# core2.net
KiCad netlist of a schematic drawn in EAGLE
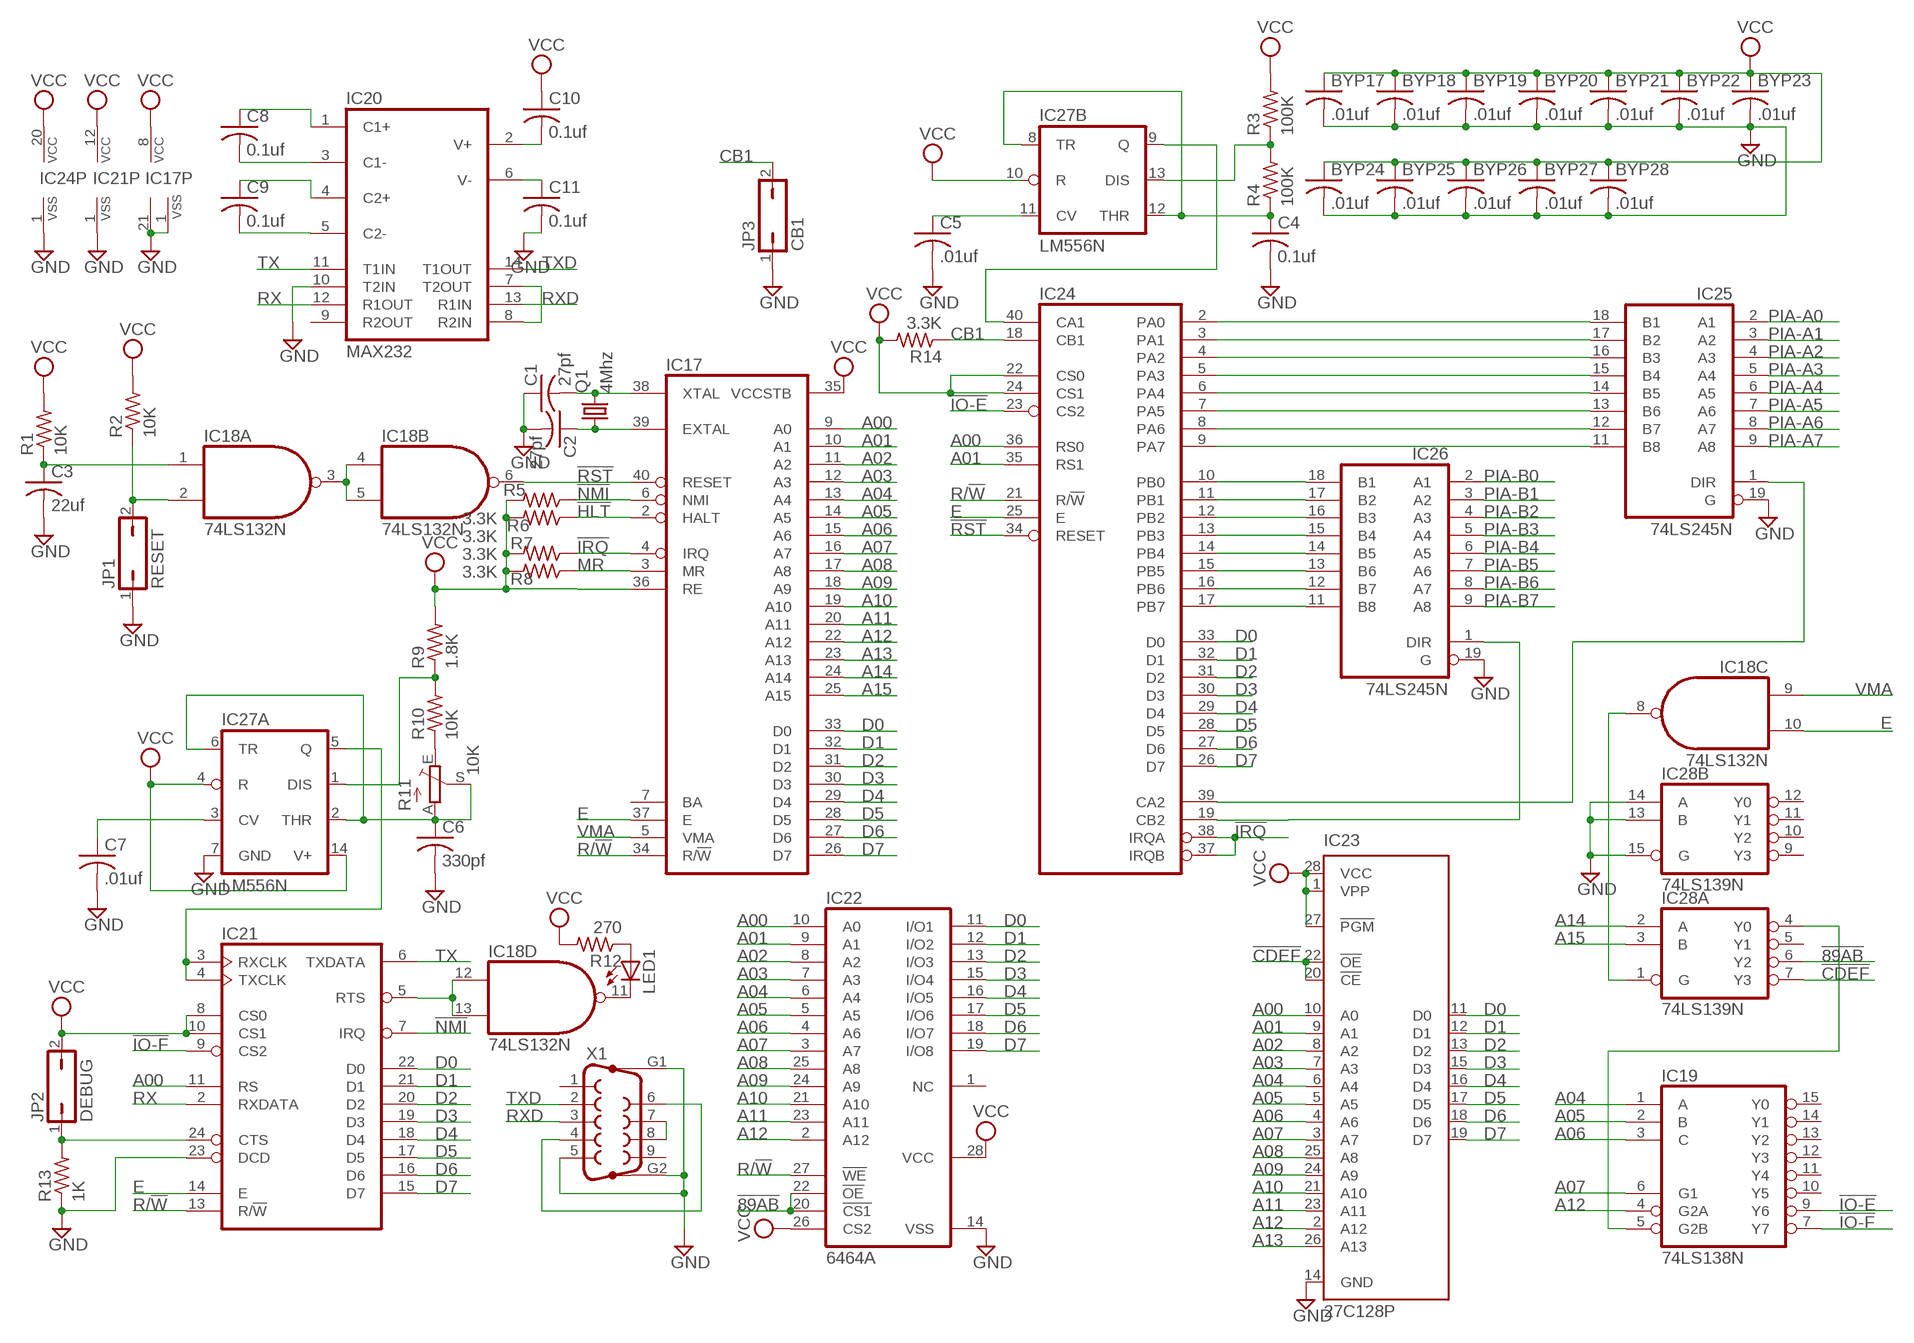
[diagram p0: schematic, sheet 1]
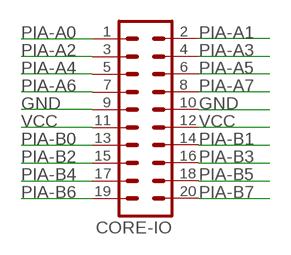
[diagram p1: schematic, sheet 2]

(export (version "E")
  (design (tool "Eeschema 10.0.6"))
  (components
    (comp (ref "CORE-IO")
      (value "MA10-2")
      (footprint "eagle-import:MA10-2")
      (libsource (lib "eagle-import") (part "MA10-2"))
    )
    (comp (ref "BYP17")
      (value ".01uf")
      (footprint "eagle-import:C050-025X075")
      (libsource (lib "eagle-import") (part "C-US050-025X075"))
    )
    (comp (ref "BYP18")
      (value ".01uf")
      (footprint "eagle-import:C050-025X075")
      (libsource (lib "eagle-import") (part "C-US050-025X075"))
    )
    (comp (ref "BYP19")
      (value ".01uf")
      (footprint "eagle-import:C050-025X075")
      (libsource (lib "eagle-import") (part "C-US050-025X075"))
    )
    (comp (ref "BYP20")
      (value ".01uf")
      (footprint "eagle-import:C050-025X075")
      (libsource (lib "eagle-import") (part "C-US050-025X075"))
    )
    (comp (ref "BYP21")
      (value ".01uf")
      (footprint "eagle-import:C050-025X075")
      (libsource (lib "eagle-import") (part "C-US050-025X075"))
    )
    (comp (ref "BYP22")
      (value ".01uf")
      (footprint "eagle-import:C050-025X075")
      (libsource (lib "eagle-import") (part "C-US050-025X075"))
    )
    (comp (ref "BYP23")
      (value ".01uf")
      (footprint "eagle-import:C050-025X075")
      (libsource (lib "eagle-import") (part "C-US050-025X075"))
    )
    (comp (ref "BYP24")
      (value ".01uf")
      (footprint "eagle-import:C050-025X075")
      (libsource (lib "eagle-import") (part "C-US050-025X075"))
    )
    (comp (ref "BYP25")
      (value ".01uf")
      (footprint "eagle-import:C050-025X075")
      (libsource (lib "eagle-import") (part "C-US050-025X075"))
    )
    (comp (ref "BYP26")
      (value ".01uf")
      (footprint "eagle-import:C050-025X075")
      (libsource (lib "eagle-import") (part "C-US050-025X075"))
    )
    (comp (ref "BYP27")
      (value ".01uf")
      (footprint "eagle-import:C050-025X075")
      (libsource (lib "eagle-import") (part "C-US050-025X075"))
    )
    (comp (ref "BYP28")
      (value ".01uf")
      (footprint "eagle-import:C050-025X075")
      (libsource (lib "eagle-import") (part "C-US050-025X075"))
    )
    (comp (ref "C1")
      (value "27pf")
      (footprint "eagle-import:C050-025X075")
      (libsource (lib "eagle-import") (part "C-US050-025X075"))
    )
    (comp (ref "C2")
      (value "27pf")
      (footprint "eagle-import:C050-025X075")
      (libsource (lib "eagle-import") (part "C-US050-025X075"))
    )
    (comp (ref "C3")
      (value "22uf")
      (footprint "eagle-import:C102-043X133")
      (libsource (lib "eagle-import") (part "C-US102-043X133"))
    )
    (comp (ref "C4")
      (value "0.1uf")
      (footprint "eagle-import:C050-025X075")
      (libsource (lib "eagle-import") (part "C-US050-025X075"))
    )
    (comp (ref "C5")
      (value ".01uf")
      (footprint "eagle-import:C050-025X075")
      (libsource (lib "eagle-import") (part "C-US050-025X075"))
    )
    (comp (ref "C6")
      (value "330pf")
      (footprint "eagle-import:C050-025X075")
      (libsource (lib "eagle-import") (part "C-US050-025X075"))
    )
    (comp (ref "C7")
      (value ".01uf")
      (footprint "eagle-import:C050-025X075")
      (libsource (lib "eagle-import") (part "C-US050-025X075"))
    )
    (comp (ref "C8")
      (value "0.1uf")
      (footprint "eagle-import:C050-025X075")
      (libsource (lib "eagle-import") (part "C-US050-025X075"))
    )
    (comp (ref "C9")
      (value "0.1uf")
      (footprint "eagle-import:C050-025X075")
      (libsource (lib "eagle-import") (part "C-US050-025X075"))
    )
    (comp (ref "C10")
      (value "0.1uf")
      (footprint "eagle-import:C050-025X075")
      (libsource (lib "eagle-import") (part "C-US050-025X075"))
    )
    (comp (ref "C11")
      (value "0.1uf")
      (footprint "eagle-import:C050-025X075")
      (libsource (lib "eagle-import") (part "C-US050-025X075"))
    )
    (comp (ref "IC17")
      (value "6802")
      (footprint "eagle-import:DIL40")
      (libsource (lib "eagle-import") (part "6802"))
    )
    (comp (ref "IC18")
      (value "74LS132N")
      (footprint "eagle-import:DIL14")
      (libsource (lib "eagle-import") (part "7400NLS"))
    )
    (comp (ref "IC19")
      (value "74LS138N")
      (footprint "eagle-import:DIL16")
      (libsource (lib "eagle-import") (part "74138NLS"))
    )
    (comp (ref "IC20")
      (value "MAX232")
      (footprint "eagle-import:DIL16")
      (fields (field (name "MF") "MAXIM") (field (name "MPN") "MAX232ACPE+"))
      (libsource (lib "eagle-import") (part "MAX232"))
    )
    (comp (ref "IC21")
      (value "6850")
      (footprint "eagle-import:DIL24")
      (fields (field (name "MF") "NTE ELECTRONICS") (field (name "MPN") "NTE6850"))
      (libsource (lib "eagle-import") (part "6850"))
    )
    (comp (ref "IC22")
      (value "6464A")
      (footprint "eagle-import:DIL28-6")
      (libsource (lib "eagle-import") (part "6264A"))
    )
    (comp (ref "IC23")
      (value "27C128P")
      (footprint "eagle-import:DIL28-6")
      (libsource (lib "eagle-import") (part "27128PC"))
    )
    (comp (ref "IC24")
      (value "6821")
      (footprint "eagle-import:DIL40")
      (fields (field (name "MF") "NTE ELECTRONICS") (field (name "MPN") "NTE6821"))
      (libsource (lib "eagle-import") (part "6821"))
    )
    (comp (ref "IC25")
      (value "74LS245N")
      (footprint "eagle-import:DIL20")
      (libsource (lib "eagle-import") (part "74245NLS"))
    )
    (comp (ref "IC26")
      (value "74LS245N")
      (footprint "eagle-import:DIL20")
      (libsource (lib "eagle-import") (part "74245NLS"))
    )
    (comp (ref "IC27")
      (value "LM556N")
      (footprint "eagle-import:DIL14")
      (libsource (lib "eagle-import") (part "556NLM"))
    )
    (comp (ref "IC28")
      (value "74LS139N")
      (footprint "eagle-import:DIL16")
      (libsource (lib "eagle-import") (part "74139NLS"))
    )
    (comp (ref "JP1")
      (value "RESET")
      (footprint "eagle-import:JP1")
      (libsource (lib "eagle-import") (part "JP1Q"))
    )
    (comp (ref "JP2")
      (value "DEBUG")
      (footprint "eagle-import:JP1")
      (libsource (lib "eagle-import") (part "JP1Q"))
    )
    (comp (ref "JP3")
      (value "CB1")
      (footprint "eagle-import:JP1")
      (libsource (lib "eagle-import") (part "JP1Q"))
    )
    (comp (ref "LED1")
      (value "LED3MM")
      (footprint "eagle-import:LED3MM")
      (libsource (lib "eagle-import") (part "LED3MM"))
    )
    (comp (ref "Q1")
      (value "4Mhz")
      (footprint "eagle-import:HC18U-V")
      (libsource (lib "eagle-import") (part "CRYSTALHC18U-V"))
    )
    (comp (ref "R1")
      (value "10K")
      (footprint "eagle-import:0207_7")
      (libsource (lib "eagle-import") (part "R-US_0207/7"))
    )
    (comp (ref "R2")
      (value "10K")
      (footprint "eagle-import:0207_7")
      (libsource (lib "eagle-import") (part "R-US_0207/7"))
    )
    (comp (ref "R3")
      (value "100K")
      (footprint "eagle-import:0207_7")
      (libsource (lib "eagle-import") (part "R-US_0207/7"))
    )
    (comp (ref "R4")
      (value "100K")
      (footprint "eagle-import:0207_7")
      (libsource (lib "eagle-import") (part "R-US_0207/7"))
    )
    (comp (ref "R5")
      (value "3.3K")
      (footprint "eagle-import:0207_7")
      (libsource (lib "eagle-import") (part "R-US_0207/7"))
    )
    (comp (ref "R6")
      (value "3.3K")
      (footprint "eagle-import:0207_7")
      (libsource (lib "eagle-import") (part "R-US_0207/7"))
    )
    (comp (ref "R7")
      (value "3.3K")
      (footprint "eagle-import:0207_7")
      (libsource (lib "eagle-import") (part "R-US_0207/7"))
    )
    (comp (ref "R8")
      (value "3.3K")
      (footprint "eagle-import:0207_7")
      (libsource (lib "eagle-import") (part "R-US_0207/7"))
    )
    (comp (ref "R9")
      (value "1.8K")
      (footprint "eagle-import:0207_7")
      (libsource (lib "eagle-import") (part "R-US_0207/7"))
    )
    (comp (ref "R10")
      (value "10K")
      (footprint "eagle-import:0207_7")
      (libsource (lib "eagle-import") (part "R-US_0207/7"))
    )
    (comp (ref "R11")
      (value "10K")
      (footprint "eagle-import:SP19L")
      (libsource (lib "eagle-import") (part "TRIM_EU-B90P"))
    )
    (comp (ref "R12")
      (value "270")
      (footprint "eagle-import:0207_7")
      (libsource (lib "eagle-import") (part "R-US_0207/7"))
    )
    (comp (ref "R13")
      (value "1K")
      (footprint "eagle-import:0207_7")
      (libsource (lib "eagle-import") (part "R-US_0207/7"))
    )
    (comp (ref "R14")
      (value "3.3K")
      (footprint "eagle-import:0207_7")
      (libsource (lib "eagle-import") (part "R-US_0207/7"))
    )
    (comp (ref "X1")
      (value "F09HP")
      (footprint "eagle-import:F09HP")
      (libsource (lib "eagle-import") (part "F09HP"))
    )
  )
  (nets
    (net (code "1") (name "A00") (class "Default")
      (node (ref "IC17") (pin "9") (pinfunction "A0_9") (pintype "output"))
      (node (ref "IC21") (pin "11") (pinfunction "RS_11") (pintype "input"))
      (node (ref "IC22") (pin "10") (pinfunction "A0_10") (pintype "input"))
      (node (ref "IC23") (pin "10") (pinfunction "A0_10") (pintype "input"))
      (node (ref "IC24") (pin "36") (pinfunction "RS0_36") (pintype "input"))
    )
    (net (code "2") (name "A01") (class "Default")
      (node (ref "IC17") (pin "10") (pinfunction "A1_10") (pintype "output"))
      (node (ref "IC22") (pin "9") (pinfunction "A1_9") (pintype "input"))
      (node (ref "IC23") (pin "9") (pinfunction "A1_9") (pintype "input"))
      (node (ref "IC24") (pin "35") (pinfunction "RS1_35") (pintype "input"))
    )
    (net (code "3") (name "A02") (class "Default")
      (node (ref "IC17") (pin "11") (pinfunction "A2_11") (pintype "output"))
      (node (ref "IC22") (pin "8") (pinfunction "A2_8") (pintype "input"))
      (node (ref "IC23") (pin "8") (pinfunction "A2_8") (pintype "input"))
    )
    (net (code "4") (name "A03") (class "Default")
      (node (ref "IC17") (pin "12") (pinfunction "A3_12") (pintype "output"))
      (node (ref "IC22") (pin "7") (pinfunction "A3_7") (pintype "input"))
      (node (ref "IC23") (pin "7") (pinfunction "A3_7") (pintype "input"))
    )
    (net (code "5") (name "A04") (class "Default")
      (node (ref "IC17") (pin "13") (pinfunction "A4_13") (pintype "output"))
      (node (ref "IC19") (pin "1") (pinfunction "A_1") (pintype "input"))
      (node (ref "IC22") (pin "6") (pinfunction "A4_6") (pintype "input"))
      (node (ref "IC23") (pin "6") (pinfunction "A4_6") (pintype "input"))
    )
    (net (code "6") (name "A05") (class "Default")
      (node (ref "IC17") (pin "14") (pinfunction "A5_14") (pintype "output"))
      (node (ref "IC19") (pin "2") (pinfunction "B_2") (pintype "input"))
      (node (ref "IC22") (pin "5") (pinfunction "A5_5") (pintype "input"))
      (node (ref "IC23") (pin "5") (pinfunction "A5_5") (pintype "input"))
    )
    (net (code "7") (name "A06") (class "Default")
      (node (ref "IC17") (pin "15") (pinfunction "A6_15") (pintype "output"))
      (node (ref "IC19") (pin "3") (pinfunction "C_3") (pintype "input"))
      (node (ref "IC22") (pin "4") (pinfunction "A6_4") (pintype "input"))
      (node (ref "IC23") (pin "4") (pinfunction "A6_4") (pintype "input"))
    )
    (net (code "8") (name "A07") (class "Default")
      (node (ref "IC17") (pin "16") (pinfunction "A7_16") (pintype "output"))
      (node (ref "IC19") (pin "6") (pinfunction "G1_6") (pintype "input"))
      (node (ref "IC22") (pin "3") (pinfunction "A7_3") (pintype "input"))
      (node (ref "IC23") (pin "3") (pinfunction "A7_3") (pintype "input"))
    )
    (net (code "9") (name "A08") (class "Default")
      (node (ref "IC17") (pin "17") (pinfunction "A8_17") (pintype "output"))
      (node (ref "IC22") (pin "25") (pinfunction "A8_25") (pintype "input"))
      (node (ref "IC23") (pin "25") (pinfunction "A8_25") (pintype "input"))
    )
    (net (code "10") (name "A09") (class "Default")
      (node (ref "IC17") (pin "18") (pinfunction "A9_18") (pintype "output"))
      (node (ref "IC22") (pin "24") (pinfunction "A9_24") (pintype "input"))
      (node (ref "IC23") (pin "24") (pinfunction "A9_24") (pintype "input"))
    )
    (net (code "11") (name "A10") (class "Default")
      (node (ref "IC17") (pin "19") (pinfunction "A10_19") (pintype "output"))
      (node (ref "IC22") (pin "21") (pinfunction "A10_21") (pintype "input"))
      (node (ref "IC23") (pin "21") (pinfunction "A10_21") (pintype "input"))
    )
    (net (code "12") (name "A11") (class "Default")
      (node (ref "IC17") (pin "20") (pinfunction "A11_20") (pintype "output"))
      (node (ref "IC22") (pin "23") (pinfunction "A11_23") (pintype "input"))
      (node (ref "IC23") (pin "23") (pinfunction "A11_23") (pintype "input"))
    )
    (net (code "13") (name "A12") (class "Default")
      (node (ref "IC17") (pin "22") (pinfunction "A12_22") (pintype "output"))
      (node (ref "IC19") (pin "4") (pinfunction "G2A_4") (pintype "input"))
      (node (ref "IC22") (pin "2") (pinfunction "A12_2") (pintype "input"))
      (node (ref "IC23") (pin "2") (pinfunction "A12_2") (pintype "input"))
    )
    (net (code "14") (name "A13") (class "Default")
      (node (ref "IC17") (pin "23") (pinfunction "A13_23") (pintype "output"))
      (node (ref "IC23") (pin "26") (pinfunction "A13_26") (pintype "input"))
    )
    (net (code "15") (name "A14") (class "Default")
      (node (ref "IC17") (pin "24") (pinfunction "A14_24") (pintype "output"))
      (node (ref "IC28") (pin "2") (pinfunction "A_2") (pintype "input"))
    )
    (net (code "16") (name "A15") (class "Default")
      (node (ref "IC17") (pin "25") (pinfunction "A15_25") (pintype "output"))
      (node (ref "IC28") (pin "3") (pinfunction "B_3") (pintype "input"))
    )
    (net (code "17") (name "CB1") (class "Default")
      (node (ref "IC24") (pin "18") (pinfunction "CB1_18") (pintype "input"))
      (node (ref "JP3") (pin "2") (pinfunction "2_2") (pintype "passive"))
      (node (ref "R14") (pin "1") (pinfunction "1_1") (pintype "passive"))
    )
    (net (code "18") (name "D0") (class "Default")
      (node (ref "IC17") (pin "33") (pinfunction "D0_33") (pintype "bidirectional"))
      (node (ref "IC21") (pin "22") (pinfunction "D0_22") (pintype "bidirectional"))
      (node (ref "IC22") (pin "11") (pinfunction "I/O1_11") (pintype "bidirectional"))
      (node (ref "IC23") (pin "11") (pinfunction "D0_11") (pintype "tri_state"))
      (node (ref "IC24") (pin "33") (pinfunction "D0_33") (pintype "bidirectional"))
    )
    (net (code "19") (name "D1") (class "Default")
      (node (ref "IC17") (pin "32") (pinfunction "D1_32") (pintype "bidirectional"))
      (node (ref "IC21") (pin "21") (pinfunction "D1_21") (pintype "bidirectional"))
      (node (ref "IC22") (pin "12") (pinfunction "I/O2_12") (pintype "bidirectional"))
      (node (ref "IC23") (pin "12") (pinfunction "D1_12") (pintype "tri_state"))
      (node (ref "IC24") (pin "32") (pinfunction "D1_32") (pintype "bidirectional"))
    )
    (net (code "20") (name "D2") (class "Default")
      (node (ref "IC17") (pin "31") (pinfunction "D2_31") (pintype "bidirectional"))
      (node (ref "IC21") (pin "20") (pinfunction "D2_20") (pintype "bidirectional"))
      (node (ref "IC22") (pin "13") (pinfunction "I/O3_13") (pintype "bidirectional"))
      (node (ref "IC23") (pin "13") (pinfunction "D2_13") (pintype "tri_state"))
      (node (ref "IC24") (pin "31") (pinfunction "D2_31") (pintype "bidirectional"))
    )
    (net (code "21") (name "D3") (class "Default")
      (node (ref "IC17") (pin "30") (pinfunction "D3_30") (pintype "bidirectional"))
      (node (ref "IC21") (pin "19") (pinfunction "D3_19") (pintype "bidirectional"))
      (node (ref "IC22") (pin "15") (pinfunction "I/O4_15") (pintype "bidirectional"))
      (node (ref "IC23") (pin "15") (pinfunction "D3_15") (pintype "tri_state"))
      (node (ref "IC24") (pin "30") (pinfunction "D3_30") (pintype "bidirectional"))
    )
    (net (code "22") (name "D4") (class "Default")
      (node (ref "IC17") (pin "29") (pinfunction "D4_29") (pintype "bidirectional"))
      (node (ref "IC21") (pin "18") (pinfunction "D4_18") (pintype "bidirectional"))
      (node (ref "IC22") (pin "16") (pinfunction "I/O5_16") (pintype "bidirectional"))
      (node (ref "IC23") (pin "16") (pinfunction "D4_16") (pintype "tri_state"))
      (node (ref "IC24") (pin "29") (pinfunction "D4_29") (pintype "bidirectional"))
    )
    (net (code "23") (name "D5") (class "Default")
      (node (ref "IC17") (pin "28") (pinfunction "D5_28") (pintype "bidirectional"))
      (node (ref "IC21") (pin "17") (pinfunction "D5_17") (pintype "bidirectional"))
      (node (ref "IC22") (pin "17") (pinfunction "I/O6_17") (pintype "bidirectional"))
      (node (ref "IC23") (pin "17") (pinfunction "D5_17") (pintype "tri_state"))
      (node (ref "IC24") (pin "28") (pinfunction "D5_28") (pintype "bidirectional"))
    )
    (net (code "24") (name "D6") (class "Default")
      (node (ref "IC17") (pin "27") (pinfunction "D6_27") (pintype "bidirectional"))
      (node (ref "IC21") (pin "16") (pinfunction "D6_16") (pintype "bidirectional"))
      (node (ref "IC22") (pin "18") (pinfunction "I/O7_18") (pintype "bidirectional"))
      (node (ref "IC23") (pin "18") (pinfunction "D6_18") (pintype "tri_state"))
      (node (ref "IC24") (pin "27") (pinfunction "D6_27") (pintype "bidirectional"))
    )
    (net (code "25") (name "D7") (class "Default")
      (node (ref "IC17") (pin "26") (pinfunction "D7_26") (pintype "bidirectional"))
      (node (ref "IC21") (pin "15") (pinfunction "D7_15") (pintype "bidirectional"))
      (node (ref "IC22") (pin "19") (pinfunction "I/O8_19") (pintype "bidirectional"))
      (node (ref "IC23") (pin "19") (pinfunction "D7_19") (pintype "tri_state"))
      (node (ref "IC24") (pin "26") (pinfunction "D7_26") (pintype "bidirectional"))
    )
    (net (code "26") (name "E") (class "Default")
      (node (ref "IC17") (pin "37") (pinfunction "E_37") (pintype "output"))
      (node (ref "IC18") (pin "10") (pinfunction "I1_10") (pintype "input"))
      (node (ref "IC21") (pin "14") (pinfunction "E_14") (pintype "input"))
      (node (ref "IC24") (pin "25") (pinfunction "E_25") (pintype "input"))
    )
    (net (code "27") (name "GND") (class "Default")
      (node (ref "BYP17") (pin "2") (pinfunction "2_2") (pintype "passive"))
      (node (ref "BYP18") (pin "2") (pinfunction "2_2") (pintype "passive"))
      (node (ref "BYP19") (pin "2") (pinfunction "2_2") (pintype "passive"))
      (node (ref "BYP20") (pin "2") (pinfunction "2_2") (pintype "passive"))
      (node (ref "BYP21") (pin "2") (pinfunction "2_2") (pintype "passive"))
      (node (ref "BYP22") (pin "2") (pinfunction "2_2") (pintype "passive"))
      (node (ref "BYP23") (pin "2") (pinfunction "2_2") (pintype "passive"))
      (node (ref "BYP24") (pin "2") (pinfunction "2_2") (pintype "passive"))
      (node (ref "BYP25") (pin "2") (pinfunction "2_2") (pintype "passive"))
      (node (ref "BYP26") (pin "2") (pinfunction "2_2") (pintype "passive"))
      (node (ref "BYP27") (pin "2") (pinfunction "2_2") (pintype "passive"))
      (node (ref "BYP28") (pin "2") (pinfunction "2_2") (pintype "passive"))
      (node (ref "C1") (pin "1") (pinfunction "1_1") (pintype "passive"))
      (node (ref "C11") (pin "2") (pinfunction "2_2") (pintype "passive"))
      (node (ref "C2") (pin "2") (pinfunction "2_2") (pintype "passive"))
      (node (ref "C3") (pin "2") (pinfunction "2_2") (pintype "passive"))
      (node (ref "C4") (pin "2") (pinfunction "2_2") (pintype "passive"))
      (node (ref "C5") (pin "2") (pinfunction "2_2") (pintype "passive"))
      (node (ref "C6") (pin "2") (pinfunction "2_2") (pintype "passive"))
      (node (ref "C7") (pin "2") (pinfunction "2_2") (pintype "passive"))
      (node (ref "CORE-IO") (pin "10") (pinfunction "10_10") (pintype "passive"))
      (node (ref "CORE-IO") (pin "9") (pinfunction "9_9") (pintype "passive"))
      (node (ref "IC17") (pin "1") (pinfunction "VSS_1") (pintype "power_in"))
      (node (ref "IC17") (pin "21") (pinfunction "VSS_21") (pintype "power_in"))
      (node (ref "IC20") (pin "10") (pinfunction "T2IN_10") (pintype "input"))
      (node (ref "IC21") (pin "1") (pinfunction "VSS_1") (pintype "power_in"))
      (node (ref "IC21") (pin "23") (pinfunction "DCD_23") (pintype "input"))
      (node (ref "IC22") (pin "14") (pinfunction "VSS_14") (pintype "power_in"))
      (node (ref "IC23") (pin "14") (pinfunction "GND_14") (pintype "power_in"))
      (node (ref "IC24") (pin "1") (pinfunction "VSS_1") (pintype "power_in"))
      (node (ref "IC25") (pin "19") (pinfunction "G_19") (pintype "input"))
      (node (ref "IC26") (pin "19") (pinfunction "G_19") (pintype "input"))
      (node (ref "IC27") (pin "7") (pinfunction "GND_7") (pintype "power_in"))
      (node (ref "IC28") (pin "13") (pinfunction "B_13") (pintype "input"))
      (node (ref "IC28") (pin "14") (pinfunction "A_14") (pintype "input"))
      (node (ref "IC28") (pin "15") (pinfunction "G_15") (pintype "input"))
      (node (ref "JP1") (pin "1") (pinfunction "1_1") (pintype "passive"))
      (node (ref "JP3") (pin "1") (pinfunction "1_1") (pintype "passive"))
      (node (ref "R13") (pin "1") (pinfunction "1_1") (pintype "passive"))
      (node (ref "X1") (pin "5") (pinfunction "5_5") (pintype "passive"))
      (node (ref "X1") (pin "G1") (pinfunction "G1_G1") (pintype "passive"))
      (node (ref "X1") (pin "G2") (pinfunction "G2_G2") (pintype "passive"))
    )
    (net (code "28") (name "MR") (class "Default")
      (node (ref "IC17") (pin "3") (pinfunction "MR_3") (pintype "input"))
      (node (ref "R8") (pin "1") (pinfunction "1_1") (pintype "passive"))
    )
    (net (code "29") (name "Net-(IC17A-EXTAL)") (class "Default")
      (node (ref "C2") (pin "1") (pinfunction "1_1") (pintype "passive"))
      (node (ref "IC17") (pin "39") (pinfunction "EXTAL_39") (pintype "input"))
      (node (ref "Q1") (pin "1") (pinfunction "1_1") (pintype "passive"))
    )
    (net (code "30") (name "Net-(IC17A-XTAL)") (class "Default")
      (node (ref "C1") (pin "2") (pinfunction "2_2") (pintype "passive"))
      (node (ref "IC17") (pin "38") (pinfunction "XTAL_38") (pintype "input"))
      (node (ref "Q1") (pin "2") (pinfunction "2_2") (pintype "passive"))
    )
    (net (code "31") (name "Net-(IC18A-I0)") (class "Default")
      (node (ref "C3") (pin "1") (pinfunction "1_1") (pintype "passive"))
      (node (ref "IC18") (pin "1") (pinfunction "I0_1") (pintype "input"))
      (node (ref "R1") (pin "1") (pinfunction "1_1") (pintype "passive"))
    )
    (net (code "32") (name "Net-(IC18A-I1)") (class "Default")
      (node (ref "IC18") (pin "2") (pinfunction "I1_2") (pintype "input"))
      (node (ref "JP1") (pin "2") (pinfunction "2_2") (pintype "passive"))
      (node (ref "R2") (pin "1") (pinfunction "1_1") (pintype "passive"))
    )
    (net (code "33") (name "Net-(IC18A-O)") (class "Default")
      (node (ref "IC18") (pin "3") (pinfunction "O_3") (pintype "output"))
      (node (ref "IC18") (pin "4") (pinfunction "I0_4") (pintype "input"))
      (node (ref "IC18") (pin "5") (pinfunction "I1_5") (pintype "input"))
    )
    (net (code "34") (name "Net-(IC18C-O)") (class "Default")
      (node (ref "IC18") (pin "8") (pinfunction "O_8") (pintype "output"))
      (node (ref "IC28") (pin "1") (pinfunction "G_1") (pintype "input"))
    )
    (net (code "35") (name "Net-(IC18D-I0)") (class "Default")
      (node (ref "IC18") (pin "12") (pinfunction "I0_12") (pintype "input"))
      (node (ref "IC18") (pin "13") (pinfunction "I1_13") (pintype "input"))
      (node (ref "IC21") (pin "5") (pinfunction "RTS_5") (pintype "output"))
    )
    (net (code "36") (name "Net-(IC18D-O)") (class "Default")
      (node (ref "IC18") (pin "11") (pinfunction "O_11") (pintype "output"))
      (node (ref "LED1") (pin "K") (pinfunction "C_K") (pintype "passive"))
    )
    (net (code "37") (name "Net-(IC19A-G2B)") (class "Default")
      (node (ref "IC19") (pin "5") (pinfunction "G2B_5") (pintype "input"))
      (node (ref "IC28") (pin "4") (pinfunction "Y0_4") (pintype "output"))
    )
    (net (code "38") (name "Net-(IC20A-C1+)") (class "Default")
      (node (ref "C8") (pin "1") (pinfunction "1_1") (pintype "passive"))
      (node (ref "IC20") (pin "1") (pinfunction "C1+_1") (pintype "bidirectional"))
    )
    (net (code "39") (name "Net-(IC20A-C1-)") (class "Default")
      (node (ref "C8") (pin "2") (pinfunction "2_2") (pintype "passive"))
      (node (ref "IC20") (pin "3") (pinfunction "C1-_3") (pintype "bidirectional"))
    )
    (net (code "40") (name "Net-(IC20A-C2+)") (class "Default")
      (node (ref "C9") (pin "1") (pinfunction "1_1") (pintype "passive"))
      (node (ref "IC20") (pin "4") (pinfunction "C2+_4") (pintype "bidirectional"))
    )
    (net (code "41") (name "Net-(IC20A-C2-)") (class "Default")
      (node (ref "C9") (pin "2") (pinfunction "2_2") (pintype "passive"))
      (node (ref "IC20") (pin "5") (pinfunction "C2-_5") (pintype "bidirectional"))
    )
    (net (code "42") (name "Net-(IC20A-R2IN)") (class "Default")
      (node (ref "IC20") (pin "7") (pinfunction "T2OUT_7") (pintype "output"))
      (node (ref "IC20") (pin "8") (pinfunction "R2IN_8") (pintype "input"))
    )
    (net (code "43") (name "Net-(IC20A-V+)") (class "Default")
      (node (ref "C10") (pin "2") (pinfunction "2_2") (pintype "passive"))
      (node (ref "IC20") (pin "2") (pinfunction "V+_2") (pintype "bidirectional"))
    )
    (net (code "44") (name "Net-(IC20A-V-)") (class "Default")
      (node (ref "C11") (pin "1") (pinfunction "1_1") (pintype "passive"))
      (node (ref "IC20") (pin "6") (pinfunction "V-_6") (pintype "bidirectional"))
    )
    (net (code "45") (name "Net-(IC21A-CTS)") (class "Default")
      (node (ref "IC21") (pin "24") (pinfunction "CTS_24") (pintype "input"))
      (node (ref "JP2") (pin "1") (pinfunction "1_1") (pintype "passive"))
      (node (ref "R13") (pin "2") (pinfunction "2_2") (pintype "passive"))
    )
    (net (code "46") (name "Net-(IC21A-RXCLK)") (class "Default")
      (node (ref "IC21") (pin "3") (pinfunction "RXCLK_3") (pintype "input"))
      (node (ref "IC21") (pin "4") (pinfunction "TXCLK_4") (pintype "input"))
      (node (ref "IC27") (pin "5") (pinfunction "Q_5") (pintype "output"))
    )
    (net (code "47") (name "Net-(IC24A-CA1)") (class "Default")
      (node (ref "IC24") (pin "40") (pinfunction "CA1_40") (pintype "input"))
      (node (ref "IC27") (pin "9") (pinfunction "Q_9") (pintype "output"))
    )
    (net (code "48") (name "Net-(IC24A-CA2)") (class "Default")
      (node (ref "IC24") (pin "39") (pinfunction "CA2_39") (pintype "bidirectional"))
      (node (ref "IC25") (pin "1") (pinfunction "DIR_1") (pintype "input"))
    )
    (net (code "49") (name "Net-(IC24A-CB2)") (class "Default")
      (node (ref "IC24") (pin "19") (pinfunction "CB2_19") (pintype "bidirectional"))
      (node (ref "IC26") (pin "1") (pinfunction "DIR_1") (pintype "input"))
    )
    (net (code "50") (name "Net-(IC24A-PA0)") (class "Default")
      (node (ref "IC24") (pin "2") (pinfunction "PA0_2") (pintype "bidirectional"))
      (node (ref "IC25") (pin "18") (pinfunction "B1_18") (pintype "bidirectional"))
    )
    (net (code "51") (name "Net-(IC24A-PA1)") (class "Default")
      (node (ref "IC24") (pin "3") (pinfunction "PA1_3") (pintype "bidirectional"))
      (node (ref "IC25") (pin "17") (pinfunction "B2_17") (pintype "bidirectional"))
    )
    (net (code "52") (name "Net-(IC24A-PA2)") (class "Default")
      (node (ref "IC24") (pin "4") (pinfunction "PA2_4") (pintype "bidirectional"))
      (node (ref "IC25") (pin "16") (pinfunction "B3_16") (pintype "bidirectional"))
    )
    (net (code "53") (name "Net-(IC24A-PA3)") (class "Default")
      (node (ref "IC24") (pin "5") (pinfunction "PA3_5") (pintype "bidirectional"))
      (node (ref "IC25") (pin "15") (pinfunction "B4_15") (pintype "bidirectional"))
    )
    (net (code "54") (name "Net-(IC24A-PA4)") (class "Default")
      (node (ref "IC24") (pin "6") (pinfunction "PA4_6") (pintype "bidirectional"))
      (node (ref "IC25") (pin "14") (pinfunction "B5_14") (pintype "bidirectional"))
    )
    (net (code "55") (name "Net-(IC24A-PA5)") (class "Default")
      (node (ref "IC24") (pin "7") (pinfunction "PA5_7") (pintype "bidirectional"))
      (node (ref "IC25") (pin "13") (pinfunction "B6_13") (pintype "bidirectional"))
    )
    (net (code "56") (name "Net-(IC24A-PA6)") (class "Default")
      (node (ref "IC24") (pin "8") (pinfunction "PA6_8") (pintype "bidirectional"))
      (node (ref "IC25") (pin "12") (pinfunction "B7_12") (pintype "bidirectional"))
    )
    (net (code "57") (name "Net-(IC24A-PA7)") (class "Default")
      (node (ref "IC24") (pin "9") (pinfunction "PA7_9") (pintype "bidirectional"))
      (node (ref "IC25") (pin "11") (pinfunction "B8_11") (pintype "bidirectional"))
    )
    (net (code "58") (name "Net-(IC24A-PB0)") (class "Default")
      (node (ref "IC24") (pin "10") (pinfunction "PB0_10") (pintype "bidirectional"))
      (node (ref "IC26") (pin "18") (pinfunction "B1_18") (pintype "bidirectional"))
    )
    (net (code "59") (name "Net-(IC24A-PB1)") (class "Default")
      (node (ref "IC24") (pin "11") (pinfunction "PB1_11") (pintype "bidirectional"))
      (node (ref "IC26") (pin "17") (pinfunction "B2_17") (pintype "bidirectional"))
    )
    (net (code "60") (name "Net-(IC24A-PB2)") (class "Default")
      (node (ref "IC24") (pin "12") (pinfunction "PB2_12") (pintype "bidirectional"))
      (node (ref "IC26") (pin "16") (pinfunction "B3_16") (pintype "bidirectional"))
    )
    (net (code "61") (name "Net-(IC24A-PB3)") (class "Default")
      (node (ref "IC24") (pin "13") (pinfunction "PB3_13") (pintype "bidirectional"))
      (node (ref "IC26") (pin "15") (pinfunction "B4_15") (pintype "bidirectional"))
    )
    (net (code "62") (name "Net-(IC24A-PB4)") (class "Default")
      (node (ref "IC24") (pin "14") (pinfunction "PB4_14") (pintype "bidirectional"))
      (node (ref "IC26") (pin "14") (pinfunction "B5_14") (pintype "bidirectional"))
    )
    (net (code "63") (name "Net-(IC24A-PB5)") (class "Default")
      (node (ref "IC24") (pin "15") (pinfunction "PB5_15") (pintype "bidirectional"))
      (node (ref "IC26") (pin "13") (pinfunction "B6_13") (pintype "bidirectional"))
    )
    (net (code "64") (name "Net-(IC24A-PB6)") (class "Default")
      (node (ref "IC24") (pin "16") (pinfunction "PB6_16") (pintype "bidirectional"))
      (node (ref "IC26") (pin "12") (pinfunction "B7_12") (pintype "bidirectional"))
    )
    (net (code "65") (name "Net-(IC24A-PB7)") (class "Default")
      (node (ref "IC24") (pin "17") (pinfunction "PB7_17") (pintype "bidirectional"))
      (node (ref "IC26") (pin "11") (pinfunction "B8_11") (pintype "bidirectional"))
    )
    (net (code "66") (name "Net-(IC27A-CV)") (class "Default")
      (node (ref "C7") (pin "1") (pinfunction "1_1") (pintype "passive"))
      (node (ref "IC27") (pin "3") (pinfunction "CV_3") (pintype "input"))
    )
    (net (code "67") (name "Net-(IC27A-DIS)") (class "Default")
      (node (ref "IC27") (pin "1") (pinfunction "DIS_1") (pintype "input"))
      (node (ref "R10") (pin "2") (pinfunction "2_2") (pintype "passive"))
      (node (ref "R9") (pin "1") (pinfunction "1_1") (pintype "passive"))
    )
    (net (code "68") (name "Net-(IC27A-THR)") (class "Default")
      (node (ref "C6") (pin "1") (pinfunction "1_1") (pintype "passive"))
      (node (ref "IC27") (pin "2") (pinfunction "THR_2") (pintype "input"))
      (node (ref "IC27") (pin "6") (pinfunction "TR_6") (pintype "input"))
      (node (ref "R11") (pin "A") (pinfunction "A_A") (pintype "passive"))
      (node (ref "R11") (pin "S") (pinfunction "S_S") (pintype "passive"))
    )
    (net (code "69") (name "Net-(IC27B-CV)") (class "Default")
      (node (ref "C5") (pin "1") (pinfunction "1_1") (pintype "passive"))
      (node (ref "IC27") (pin "11") (pinfunction "CV_11") (pintype "input"))
    )
    (net (code "70") (name "Net-(IC27B-DIS)") (class "Default")
      (node (ref "IC27") (pin "13") (pinfunction "DIS_13") (pintype "input"))
      (node (ref "R3") (pin "1") (pinfunction "1_1") (pintype "passive"))
      (node (ref "R4") (pin "2") (pinfunction "2_2") (pintype "passive"))
    )
    (net (code "71") (name "Net-(IC27B-THR)") (class "Default")
      (node (ref "C4") (pin "1") (pinfunction "1_1") (pintype "passive"))
      (node (ref "IC27") (pin "12") (pinfunction "THR_12") (pintype "input"))
      (node (ref "IC27") (pin "8") (pinfunction "TR_8") (pintype "input"))
      (node (ref "R4") (pin "1") (pinfunction "1_1") (pintype "passive"))
    )
    (net (code "72") (name "Net-(LED1-PadA)") (class "Default")
      (node (ref "LED1") (pin "A") (pinfunction "A_A") (pintype "passive"))
      (node (ref "R12") (pin "1") (pinfunction "1_1") (pintype "passive"))
    )
    (net (code "73") (name "Net-(R10-Pad1)") (class "Default")
      (node (ref "R10") (pin "1") (pinfunction "1_1") (pintype "passive"))
      (node (ref "R11") (pin "E") (pinfunction "E_E") (pintype "passive"))
    )
    (net (code "74") (name "Net-(X1-Pad4)") (class "Default")
      (node (ref "X1") (pin "4") (pinfunction "4_4") (pintype "passive"))
      (node (ref "X1") (pin "6") (pinfunction "6_6") (pintype "passive"))
    )
    (net (code "75") (name "Net-(X1-Pad7)") (class "Default")
      (node (ref "X1") (pin "7") (pinfunction "7_7") (pintype "passive"))
      (node (ref "X1") (pin "8") (pinfunction "8_8") (pintype "passive"))
    )
    (net (code "76") (name "PIA-A0") (class "Default")
      (node (ref "CORE-IO") (pin "1") (pinfunction "1_1") (pintype "passive"))
      (node (ref "IC25") (pin "2") (pinfunction "A1_2") (pintype "bidirectional"))
    )
    (net (code "77") (name "PIA-A1") (class "Default")
      (node (ref "CORE-IO") (pin "2") (pinfunction "2_2") (pintype "passive"))
      (node (ref "IC25") (pin "3") (pinfunction "A2_3") (pintype "bidirectional"))
    )
    (net (code "78") (name "PIA-A2") (class "Default")
      (node (ref "CORE-IO") (pin "3") (pinfunction "3_3") (pintype "passive"))
      (node (ref "IC25") (pin "4") (pinfunction "A3_4") (pintype "bidirectional"))
    )
    (net (code "79") (name "PIA-A3") (class "Default")
      (node (ref "CORE-IO") (pin "4") (pinfunction "4_4") (pintype "passive"))
      (node (ref "IC25") (pin "5") (pinfunction "A4_5") (pintype "bidirectional"))
    )
    (net (code "80") (name "PIA-A4") (class "Default")
      (node (ref "CORE-IO") (pin "5") (pinfunction "5_5") (pintype "passive"))
      (node (ref "IC25") (pin "6") (pinfunction "A5_6") (pintype "bidirectional"))
    )
    (net (code "81") (name "PIA-A5") (class "Default")
      (node (ref "CORE-IO") (pin "6") (pinfunction "6_6") (pintype "passive"))
      (node (ref "IC25") (pin "7") (pinfunction "A6_7") (pintype "bidirectional"))
    )
    (net (code "82") (name "PIA-A6") (class "Default")
      (node (ref "CORE-IO") (pin "7") (pinfunction "7_7") (pintype "passive"))
      (node (ref "IC25") (pin "8") (pinfunction "A7_8") (pintype "bidirectional"))
    )
    (net (code "83") (name "PIA-A7") (class "Default")
      (node (ref "CORE-IO") (pin "8") (pinfunction "8_8") (pintype "passive"))
      (node (ref "IC25") (pin "9") (pinfunction "A8_9") (pintype "bidirectional"))
    )
    (net (code "84") (name "PIA-B0") (class "Default")
      (node (ref "CORE-IO") (pin "13") (pinfunction "13_13") (pintype "passive"))
      (node (ref "IC26") (pin "2") (pinfunction "A1_2") (pintype "bidirectional"))
    )
    (net (code "85") (name "PIA-B1") (class "Default")
      (node (ref "CORE-IO") (pin "14") (pinfunction "14_14") (pintype "passive"))
      (node (ref "IC26") (pin "3") (pinfunction "A2_3") (pintype "bidirectional"))
    )
    (net (code "86") (name "PIA-B2") (class "Default")
      (node (ref "CORE-IO") (pin "15") (pinfunction "15_15") (pintype "passive"))
      (node (ref "IC26") (pin "4") (pinfunction "A3_4") (pintype "bidirectional"))
    )
    (net (code "87") (name "PIA-B3") (class "Default")
      (node (ref "CORE-IO") (pin "16") (pinfunction "16_16") (pintype "passive"))
      (node (ref "IC26") (pin "5") (pinfunction "A4_5") (pintype "bidirectional"))
    )
    (net (code "88") (name "PIA-B4") (class "Default")
      (node (ref "CORE-IO") (pin "17") (pinfunction "17_17") (pintype "passive"))
      (node (ref "IC26") (pin "6") (pinfunction "A5_6") (pintype "bidirectional"))
    )
    (net (code "89") (name "PIA-B5") (class "Default")
      (node (ref "CORE-IO") (pin "18") (pinfunction "18_18") (pintype "passive"))
      (node (ref "IC26") (pin "7") (pinfunction "A6_7") (pintype "bidirectional"))
    )
    (net (code "90") (name "PIA-B6") (class "Default")
      (node (ref "CORE-IO") (pin "19") (pinfunction "19_19") (pintype "passive"))
      (node (ref "IC26") (pin "8") (pinfunction "A7_8") (pintype "bidirectional"))
    )
    (net (code "91") (name "PIA-B7") (class "Default")
      (node (ref "CORE-IO") (pin "20") (pinfunction "20_20") (pintype "passive"))
      (node (ref "IC26") (pin "9") (pinfunction "A8_9") (pintype "bidirectional"))
    )
    (net (code "92") (name "RX") (class "Default")
      (node (ref "IC20") (pin "12") (pinfunction "R1OUT_12") (pintype "output"))
      (node (ref "IC21") (pin "2") (pinfunction "RXDATA_2") (pintype "input"))
    )
    (net (code "93") (name "RXD") (class "Default")
      (node (ref "IC20") (pin "13") (pinfunction "R1IN_13") (pintype "input"))
      (node (ref "X1") (pin "3") (pinfunction "3_3") (pintype "passive"))
    )
    (net (code "94") (name "R{slash}~{W}") (class "Default")
      (node (ref "IC17") (pin "34") (pinfunction "R/~{W}_34") (pintype "output"))
      (node (ref "IC21") (pin "13") (pinfunction "R/~{W}_13") (pintype "input"))
      (node (ref "IC22") (pin "27") (pinfunction "~{WE}_27") (pintype "input"))
      (node (ref "IC24") (pin "21") (pinfunction "R/~{W}_21") (pintype "input"))
    )
    (net (code "95") (name "TX") (class "Default")
      (node (ref "IC20") (pin "11") (pinfunction "T1IN_11") (pintype "input"))
      (node (ref "IC21") (pin "6") (pinfunction "TXDATA_6") (pintype "output"))
    )
    (net (code "96") (name "TXD") (class "Default")
      (node (ref "IC20") (pin "14") (pinfunction "T1OUT_14") (pintype "output"))
      (node (ref "X1") (pin "2") (pinfunction "2_2") (pintype "passive"))
    )
    (net (code "97") (name "VCC") (class "Default")
      (node (ref "BYP17") (pin "1") (pinfunction "1_1") (pintype "passive"))
      (node (ref "BYP18") (pin "1") (pinfunction "1_1") (pintype "passive"))
      (node (ref "BYP19") (pin "1") (pinfunction "1_1") (pintype "passive"))
      (node (ref "BYP20") (pin "1") (pinfunction "1_1") (pintype "passive"))
      (node (ref "BYP21") (pin "1") (pinfunction "1_1") (pintype "passive"))
      (node (ref "BYP22") (pin "1") (pinfunction "1_1") (pintype "passive"))
      (node (ref "BYP23") (pin "1") (pinfunction "1_1") (pintype "passive"))
      (node (ref "BYP24") (pin "1") (pinfunction "1_1") (pintype "passive"))
      (node (ref "BYP25") (pin "1") (pinfunction "1_1") (pintype "passive"))
      (node (ref "BYP26") (pin "1") (pinfunction "1_1") (pintype "passive"))
      (node (ref "BYP27") (pin "1") (pinfunction "1_1") (pintype "passive"))
      (node (ref "BYP28") (pin "1") (pinfunction "1_1") (pintype "passive"))
      (node (ref "C10") (pin "1") (pinfunction "1_1") (pintype "passive"))
      (node (ref "CORE-IO") (pin "11") (pinfunction "11_11") (pintype "passive"))
      (node (ref "CORE-IO") (pin "12") (pinfunction "12_12") (pintype "passive"))
      (node (ref "IC17") (pin "35") (pinfunction "VCCSTB_35") (pintype "input"))
      (node (ref "IC17") (pin "36") (pinfunction "RE_36") (pintype "input"))
      (node (ref "IC17") (pin "8") (pinfunction "VCC_8") (pintype "power_in"))
      (node (ref "IC21") (pin "10") (pinfunction "CS1_10") (pintype "input"))
      (node (ref "IC21") (pin "12") (pinfunction "VCC_12") (pintype "power_in"))
      (node (ref "IC21") (pin "8") (pinfunction "CS0_8") (pintype "input"))
      (node (ref "IC22") (pin "26") (pinfunction "CS2_26") (pintype "input"))
      (node (ref "IC22") (pin "28") (pinfunction "VCC_28") (pintype "power_in"))
      (node (ref "IC23") (pin "1") (pinfunction "VPP_1") (pintype "input"))
      (node (ref "IC23") (pin "27") (pinfunction "~{PGM}_27") (pintype "passive"))
      (node (ref "IC23") (pin "28") (pinfunction "VCC_28") (pintype "power_in"))
      (node (ref "IC24") (pin "20") (pinfunction "VCC_20") (pintype "power_in"))
      (node (ref "IC24") (pin "22") (pinfunction "CS0_22") (pintype "input"))
      (node (ref "IC24") (pin "24") (pinfunction "CS1_24") (pintype "input"))
      (node (ref "IC27") (pin "10") (pinfunction "R_10") (pintype "input"))
      (node (ref "IC27") (pin "14") (pinfunction "V+_14") (pintype "power_in"))
      (node (ref "IC27") (pin "4") (pinfunction "R_4") (pintype "input"))
      (node (ref "JP2") (pin "2") (pinfunction "2_2") (pintype "passive"))
      (node (ref "R1") (pin "2") (pinfunction "2_2") (pintype "passive"))
      (node (ref "R12") (pin "2") (pinfunction "2_2") (pintype "passive"))
      (node (ref "R14") (pin "2") (pinfunction "2_2") (pintype "passive"))
      (node (ref "R2") (pin "2") (pinfunction "2_2") (pintype "passive"))
      (node (ref "R3") (pin "2") (pinfunction "2_2") (pintype "passive"))
      (node (ref "R5") (pin "2") (pinfunction "2_2") (pintype "passive"))
      (node (ref "R6") (pin "2") (pinfunction "2_2") (pintype "passive"))
      (node (ref "R7") (pin "2") (pinfunction "2_2") (pintype "passive"))
      (node (ref "R8") (pin "2") (pinfunction "2_2") (pintype "passive"))
      (node (ref "R9") (pin "2") (pinfunction "2_2") (pintype "passive"))
    )
    (net (code "98") (name "VMA") (class "Default")
      (node (ref "IC17") (pin "5") (pinfunction "VMA_5") (pintype "output"))
      (node (ref "IC18") (pin "9") (pinfunction "I0_9") (pintype "input"))
    )
    (net (code "99") (name "unconnected-(IC17A-BA-Pad7)") (class "Default")
      (node (ref "IC17") (pin "7") (pinfunction "BA_7") (pintype "output"))
    )
    (net (code "100") (name "unconnected-(IC19A-Y0-Pad15)") (class "Default")
      (node (ref "IC19") (pin "15") (pinfunction "Y0_15") (pintype "output"))
    )
    (net (code "101") (name "unconnected-(IC19A-Y1-Pad14)") (class "Default")
      (node (ref "IC19") (pin "14") (pinfunction "Y1_14") (pintype "output"))
    )
    (net (code "102") (name "unconnected-(IC19A-Y2-Pad13)") (class "Default")
      (node (ref "IC19") (pin "13") (pinfunction "Y2_13") (pintype "output"))
    )
    (net (code "103") (name "unconnected-(IC19A-Y3-Pad12)") (class "Default")
      (node (ref "IC19") (pin "12") (pinfunction "Y3_12") (pintype "output"))
    )
    (net (code "104") (name "unconnected-(IC19A-Y4-Pad11)") (class "Default")
      (node (ref "IC19") (pin "11") (pinfunction "Y4_11") (pintype "output"))
    )
    (net (code "105") (name "unconnected-(IC19A-Y5-Pad10)") (class "Default")
      (node (ref "IC19") (pin "10") (pinfunction "Y5_10") (pintype "output"))
    )
    (net (code "106") (name "unconnected-(IC20A-R2OUT-Pad9)") (class "Default")
      (node (ref "IC20") (pin "9") (pinfunction "R2OUT_9") (pintype "output"))
    )
    (net (code "107") (name "unconnected-(IC22-NC-Pad1)") (class "Default")
      (node (ref "IC22") (pin "1") (pinfunction "NC_1") (pintype "no_connect"))
    )
    (net (code "108") (name "unconnected-(IC28A-Y1-Pad5)") (class "Default")
      (node (ref "IC28") (pin "5") (pinfunction "Y1_5") (pintype "output"))
    )
    (net (code "109") (name "unconnected-(IC28B-Y0-Pad12)") (class "Default")
      (node (ref "IC28") (pin "12") (pinfunction "Y0_12") (pintype "output"))
    )
    (net (code "110") (name "unconnected-(IC28B-Y1-Pad11)") (class "Default")
      (node (ref "IC28") (pin "11") (pinfunction "Y1_11") (pintype "output"))
    )
    (net (code "111") (name "unconnected-(IC28B-Y2-Pad10)") (class "Default")
      (node (ref "IC28") (pin "10") (pinfunction "Y2_10") (pintype "output"))
    )
    (net (code "112") (name "unconnected-(IC28B-Y3-Pad9)") (class "Default")
      (node (ref "IC28") (pin "9") (pinfunction "Y3_9") (pintype "output"))
    )
    (net (code "113") (name "unconnected-(X1-Pad1)") (class "Default")
      (node (ref "X1") (pin "1") (pinfunction "1_1") (pintype "passive"))
    )
    (net (code "114") (name "unconnected-(X1-Pad9)") (class "Default")
      (node (ref "X1") (pin "9") (pinfunction "9_9") (pintype "passive"))
    )
    (net (code "115") (name "~{89AB}") (class "Default")
      (node (ref "IC22") (pin "20") (pinfunction "~{CS1}_20") (pintype "input"))
      (node (ref "IC22") (pin "22") (pinfunction "~{OE}_22") (pintype "input"))
      (node (ref "IC28") (pin "6") (pinfunction "Y2_6") (pintype "output"))
    )
    (net (code "116") (name "~{CDEF}") (class "Default")
      (node (ref "IC23") (pin "20") (pinfunction "~{CE}_20") (pintype "input"))
      (node (ref "IC23") (pin "22") (pinfunction "~{OE}_22") (pintype "input"))
      (node (ref "IC28") (pin "7") (pinfunction "Y3_7") (pintype "output"))
    )
    (net (code "117") (name "~{HLT}") (class "Default")
      (node (ref "IC17") (pin "2") (pinfunction "HALT_2") (pintype "input"))
      (node (ref "R5") (pin "1") (pinfunction "1_1") (pintype "passive"))
    )
    (net (code "118") (name "~{IO-E}") (class "Default")
      (node (ref "IC19") (pin "9") (pinfunction "Y6_9") (pintype "output"))
      (node (ref "IC24") (pin "23") (pinfunction "CS2_23") (pintype "input"))
    )
    (net (code "119") (name "~{IO-F}") (class "Default")
      (node (ref "IC19") (pin "7") (pinfunction "Y7_7") (pintype "output"))
      (node (ref "IC21") (pin "9") (pinfunction "CS2_9") (pintype "input"))
    )
    (net (code "120") (name "~{IRQ}") (class "Default")
      (node (ref "IC17") (pin "4") (pinfunction "IRQ_4") (pintype "input"))
      (node (ref "IC24") (pin "37") (pinfunction "IRQB_37") (pintype "open_collector"))
      (node (ref "IC24") (pin "38") (pinfunction "IRQA_38") (pintype "open_collector"))
      (node (ref "R7") (pin "1") (pinfunction "1_1") (pintype "passive"))
    )
    (net (code "121") (name "~{NMI}") (class "Default")
      (node (ref "IC17") (pin "6") (pinfunction "NMI_6") (pintype "input"))
      (node (ref "IC21") (pin "7") (pinfunction "IRQ_7") (pintype "output"))
      (node (ref "R6") (pin "1") (pinfunction "1_1") (pintype "passive"))
    )
    (net (code "122") (name "~{RST}") (class "Default")
      (node (ref "IC17") (pin "40") (pinfunction "RESET_40") (pintype "input"))
      (node (ref "IC18") (pin "6") (pinfunction "O_6") (pintype "output"))
      (node (ref "IC24") (pin "34") (pinfunction "RESET_34") (pintype "input"))
    )
  )
)
